# APRS-ESP32_SA8x8_Rev_B.net
KiCad netlist of a schematic drawn in EAGLE
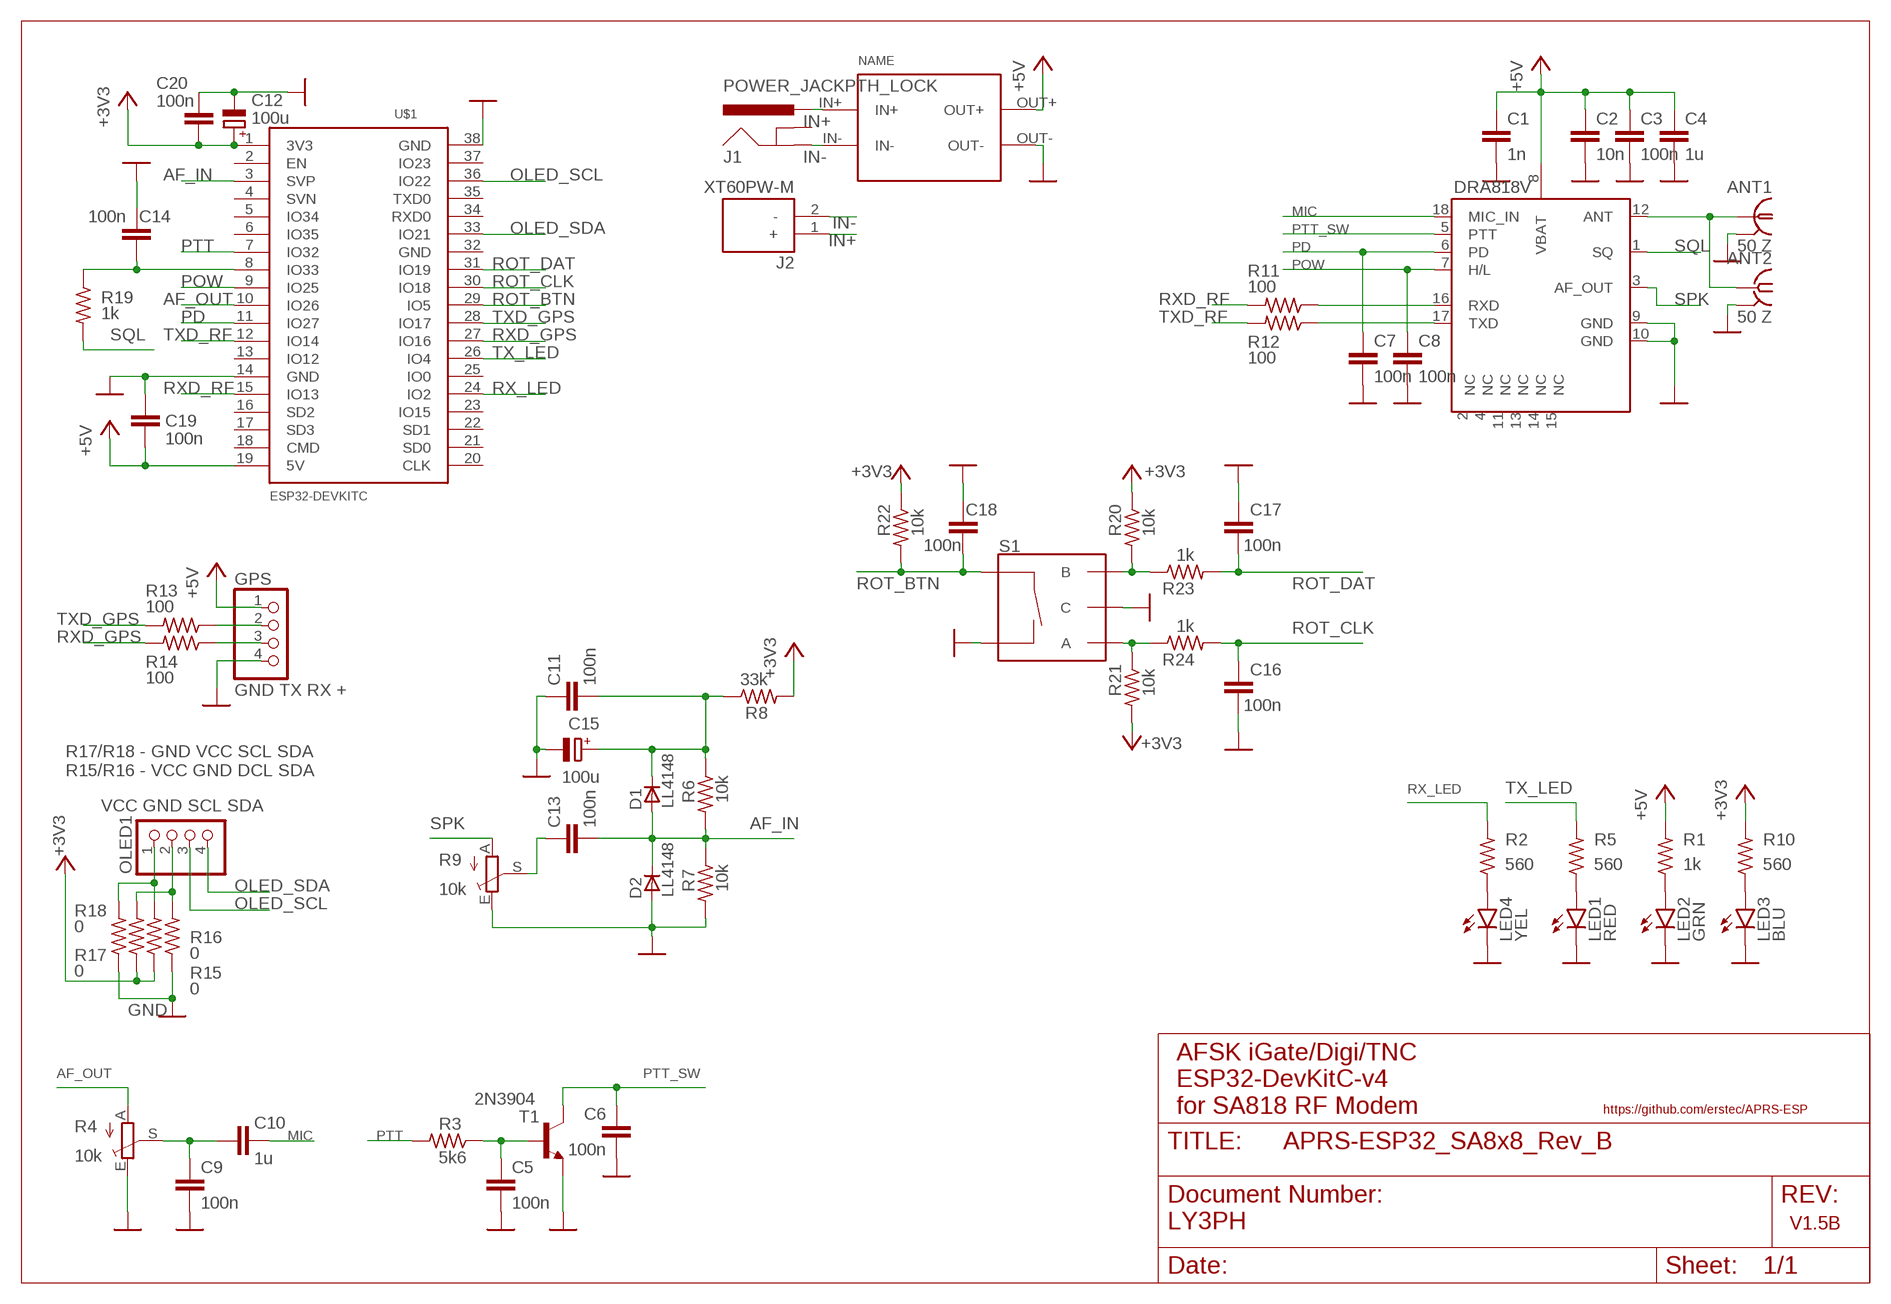
[diagram p0: schematic, sheet 1]

(export (version "E")
  (design (tool "Eeschema 10.0.6"))
  (components
    (comp (ref "ANT1")
      (value "50 Z")
      (footprint "eagle-import:LTI-SASF54GT")
      (libsource (lib "eagle-import") (part "LTI-SASF54GT"))
    )
    (comp (ref "ANT2")
      (value "50 Z")
      (footprint "eagle-import:J502-ND-142-0701-801_806")
      (fields (field (name "MF") "JOHNSON COMPONENTS") (field (name "MPN") "142-0701-801"))
      (libsource (lib "eagle-import") (part "SMA-142-0701-801/806"))
    )
    (comp (ref "C1")
      (value "1n")
      (footprint "eagle-import:C0805")
      (libsource (lib "eagle-import") (part "C-EUC0805"))
    )
    (comp (ref "C2")
      (value "10n")
      (footprint "eagle-import:C0805")
      (libsource (lib "eagle-import") (part "C-EUC0805"))
    )
    (comp (ref "C3")
      (value "100n")
      (footprint "eagle-import:C0805")
      (libsource (lib "eagle-import") (part "C-EUC0805"))
    )
    (comp (ref "C4")
      (value "1u")
      (footprint "eagle-import:C0805")
      (libsource (lib "eagle-import") (part "C-EUC0805"))
    )
    (comp (ref "C5")
      (value "100n")
      (footprint "eagle-import:C0805")
      (libsource (lib "eagle-import") (part "C-EUC0805"))
    )
    (comp (ref "C6")
      (value "100n")
      (footprint "eagle-import:C0805")
      (libsource (lib "eagle-import") (part "C-EUC0805"))
    )
    (comp (ref "C7")
      (value "100n")
      (footprint "eagle-import:C0805")
      (libsource (lib "eagle-import") (part "C-EUC0805"))
    )
    (comp (ref "C8")
      (value "100n")
      (footprint "eagle-import:C0805")
      (libsource (lib "eagle-import") (part "C-EUC0805"))
    )
    (comp (ref "C9")
      (value "100n")
      (footprint "eagle-import:C0805")
      (libsource (lib "eagle-import") (part "C-EUC0805"))
    )
    (comp (ref "C10")
      (value "1u")
      (footprint "eagle-import:C0805")
      (libsource (lib "eagle-import") (part "C-EUC0805"))
    )
    (comp (ref "C11")
      (value "100n")
      (footprint "eagle-import:C0805")
      (libsource (lib "eagle-import") (part "C-EUC0805"))
    )
    (comp (ref "C12")
      (value "100u")
      (footprint "eagle-import:SMC_D")
      (libsource (lib "eagle-import") (part "CPOL-EUSMCD"))
    )
    (comp (ref "C13")
      (value "100n")
      (footprint "eagle-import:C0805")
      (libsource (lib "eagle-import") (part "C-EUC0805"))
    )
    (comp (ref "C14")
      (value "100n")
      (footprint "eagle-import:C0805")
      (libsource (lib "eagle-import") (part "C-EUC0805"))
    )
    (comp (ref "C15")
      (value "100u")
      (footprint "eagle-import:SMC_D")
      (libsource (lib "eagle-import") (part "CPOL-EUSMCD"))
    )
    (comp (ref "C16")
      (value "100n")
      (footprint "eagle-import:C0805")
      (libsource (lib "eagle-import") (part "C-EUC0805"))
    )
    (comp (ref "C17")
      (value "100n")
      (footprint "eagle-import:C0805")
      (libsource (lib "eagle-import") (part "C-EUC0805"))
    )
    (comp (ref "C18")
      (value "100n")
      (footprint "eagle-import:C0805")
      (libsource (lib "eagle-import") (part "C-EUC0805"))
    )
    (comp (ref "C19")
      (value "100n")
      (footprint "eagle-import:C0805")
      (libsource (lib "eagle-import") (part "C-EUC0805"))
    )
    (comp (ref "C20")
      (value "100n")
      (footprint "eagle-import:C0805")
      (libsource (lib "eagle-import") (part "C-EUC0805"))
    )
    (comp (ref "D1")
      (value "LL4148")
      (footprint "eagle-import:SOD80_DO213AA_MINIMELF")
      (libsource (lib "eagle-import") (part "LL4148"))
    )
    (comp (ref "D2")
      (value "LL4148")
      (footprint "eagle-import:SOD80_DO213AA_MINIMELF")
      (libsource (lib "eagle-import") (part "LL4148"))
    )
    (comp (ref "DRA818V")
      (value "DRA818A")
      (footprint "eagle-import:DRA818A")
      (libsource (lib "eagle-import") (part "DRA818A"))
    )
    (comp (ref "GPS")
      (value "GND TX RX +")
      (footprint "eagle-import:1X04")
      (libsource (lib "eagle-import") (part "PINHD-1X4"))
    )
    (comp (ref "J1")
      (value "POWER_JACKPTH_LOCK")
      (footprint "eagle-import:POWER_JACK_PTH_LOCK")
      (libsource (lib "eagle-import") (part "POWER_JACKPTH_LOCK"))
    )
    (comp (ref "J2")
      (value "XT60PW-M")
      (footprint "eagle-import:AMASS_XT60PW-M")
      (fields (field (name "MF") "AMASS"))
      (libsource (lib "eagle-import") (part "XT60PW-M"))
    )
    (comp (ref "LED1")
      (value "RED")
      (footprint "eagle-import:CHIP-LED0805")
      (libsource (lib "eagle-import") (part "LEDCHIP-LED0805"))
    )
    (comp (ref "LED2")
      (value "GRN")
      (footprint "eagle-import:CHIP-LED0805")
      (libsource (lib "eagle-import") (part "LEDCHIP-LED0805"))
    )
    (comp (ref "LED3")
      (value "BLU")
      (footprint "eagle-import:CHIP-LED0805")
      (libsource (lib "eagle-import") (part "LEDCHIP-LED0805"))
    )
    (comp (ref "LED4")
      (value "YEL")
      (footprint "eagle-import:CHIP-LED0805")
      (libsource (lib "eagle-import") (part "LEDCHIP-LED0805"))
    )
    (comp (ref "OLED1")
      (value "VCC GND SCL SDA")
      (footprint "eagle-import:1X04")
      (libsource (lib "eagle-import") (part "PINHD-1X4"))
    )
    (comp (ref "R1")
      (value "1k")
      (footprint "eagle-import:R0805")
      (libsource (lib "eagle-import") (part "R-US_R0805"))
    )
    (comp (ref "R2")
      (value "560")
      (footprint "eagle-import:R0805")
      (libsource (lib "eagle-import") (part "R-US_R0805"))
    )
    (comp (ref "R3")
      (value "5k6")
      (footprint "eagle-import:R0805")
      (libsource (lib "eagle-import") (part "R-US_R0805"))
    )
    (comp (ref "R4")
      (value "10k")
      (footprint "eagle-import:CA6H")
      (libsource (lib "eagle-import") (part "TRIM_EU-CA6H"))
    )
    (comp (ref "R5")
      (value "560")
      (footprint "eagle-import:R0805")
      (libsource (lib "eagle-import") (part "R-US_R0805"))
    )
    (comp (ref "R6")
      (value "10k")
      (footprint "eagle-import:R0805")
      (libsource (lib "eagle-import") (part "R-US_R0805"))
    )
    (comp (ref "R7")
      (value "10k")
      (footprint "eagle-import:R0805")
      (libsource (lib "eagle-import") (part "R-US_R0805"))
    )
    (comp (ref "R8")
      (value "33k")
      (footprint "eagle-import:R0805")
      (libsource (lib "eagle-import") (part "R-US_R0805"))
    )
    (comp (ref "R9")
      (value "10k")
      (footprint "eagle-import:CA6H")
      (libsource (lib "eagle-import") (part "TRIM_EU-CA6H"))
    )
    (comp (ref "R10")
      (value "560")
      (footprint "eagle-import:R0805")
      (libsource (lib "eagle-import") (part "R-US_R0805"))
    )
    (comp (ref "R11")
      (value "100")
      (footprint "eagle-import:R0805")
      (libsource (lib "eagle-import") (part "R-US_R0805"))
    )
    (comp (ref "R12")
      (value "100")
      (footprint "eagle-import:R0805")
      (libsource (lib "eagle-import") (part "R-US_R0805"))
    )
    (comp (ref "R13")
      (value "100")
      (footprint "eagle-import:R0805")
      (libsource (lib "eagle-import") (part "R-US_R0805"))
    )
    (comp (ref "R14")
      (value "100")
      (footprint "eagle-import:R0805")
      (libsource (lib "eagle-import") (part "R-US_R0805"))
    )
    (comp (ref "R15")
      (value "0")
      (footprint "eagle-import:R0805")
      (libsource (lib "eagle-import") (part "R-US_R0805"))
    )
    (comp (ref "R16")
      (value "0")
      (footprint "eagle-import:R0805")
      (libsource (lib "eagle-import") (part "R-US_R0805"))
    )
    (comp (ref "R17")
      (value "0")
      (footprint "eagle-import:R0805")
      (libsource (lib "eagle-import") (part "R-US_R0805"))
    )
    (comp (ref "R18")
      (value "0")
      (footprint "eagle-import:R0805")
      (libsource (lib "eagle-import") (part "R-US_R0805"))
    )
    (comp (ref "R19")
      (value "1k")
      (footprint "eagle-import:R0805")
      (libsource (lib "eagle-import") (part "R-US_R0805"))
    )
    (comp (ref "R20")
      (value "10k")
      (footprint "eagle-import:R0805")
      (libsource (lib "eagle-import") (part "R-US_R0805"))
    )
    (comp (ref "R21")
      (value "10k")
      (footprint "eagle-import:R0805")
      (libsource (lib "eagle-import") (part "R-US_R0805"))
    )
    (comp (ref "R22")
      (value "10k")
      (footprint "eagle-import:R0805")
      (libsource (lib "eagle-import") (part "R-US_R0805"))
    )
    (comp (ref "R23")
      (value "1k")
      (footprint "eagle-import:R0805")
      (libsource (lib "eagle-import") (part "R-US_R0805"))
    )
    (comp (ref "R24")
      (value "1k")
      (footprint "eagle-import:R0805")
      (libsource (lib "eagle-import") (part "R-US_R0805"))
    )
    (comp (ref "S1")
      (value "ENCODER-SWITCH")
      (footprint "eagle-import:ROTARY_ENC_PLAIN")
      (libsource (lib "eagle-import") (part "ENCODER-SWITCH"))
    )
    (comp (ref "T1")
      (value "2N3904")
      (footprint "eagle-import:SOT23-BEC")
      (libsource (lib "eagle-import") (part "-NPN-SOT23-BECMMBT3904LT1"))
    )
    (comp (ref "U$1")
      (value "ESP32DEVKITC")
      (footprint "eagle-import:ESP32-DEVKITC")
      (libsource (lib "eagle-import") (part "ESP32DEVKITC"))
    )
    (comp (ref "U$2")
      (value "CP8-ADJ")
      (footprint "eagle-import:CP8-ADJ")
      (libsource (lib "eagle-import") (part "CP8-ADJ"))
    )
  )
  (nets
    (net (code "1") (name "+3V3") (class "Default")
      (node (ref "C12") (pin "+") (pinfunction "+_+") (pintype "passive"))
      (node (ref "C20") (pin "2") (pinfunction "2_2") (pintype "passive"))
      (node (ref "R10") (pin "2") (pinfunction "2_2") (pintype "passive"))
      (node (ref "R15") (pin "1") (pinfunction "1_1") (pintype "passive"))
      (node (ref "R17") (pin "1") (pinfunction "1_1") (pintype "passive"))
      (node (ref "R20") (pin "1") (pinfunction "1_1") (pintype "passive"))
      (node (ref "R21") (pin "2") (pinfunction "2_2") (pintype "passive"))
      (node (ref "R22") (pin "1") (pinfunction "1_1") (pintype "passive"))
      (node (ref "R8") (pin "2") (pinfunction "2_2") (pintype "passive"))
      (node (ref "U$1") (pin "1") (pinfunction "3V3_1") (pintype "bidirectional"))
    )
    (net (code "2") (name "+5V") (class "Default")
      (node (ref "C1") (pin "1") (pinfunction "1_1") (pintype "passive"))
      (node (ref "C19") (pin "2") (pinfunction "2_2") (pintype "passive"))
      (node (ref "C2") (pin "1") (pinfunction "1_1") (pintype "passive"))
      (node (ref "C3") (pin "1") (pinfunction "1_1") (pintype "passive"))
      (node (ref "C4") (pin "1") (pinfunction "1_1") (pintype "passive"))
      (node (ref "DRA818V") (pin "8") (pinfunction "VBAT_8") (pintype "bidirectional"))
      (node (ref "GPS") (pin "1") (pinfunction "1_1") (pintype "passive"))
      (node (ref "R1") (pin "2") (pinfunction "2_2") (pintype "passive"))
      (node (ref "U$1") (pin "19") (pinfunction "5V_19") (pintype "bidirectional"))
      (node (ref "U$2") (pin "OUT+") (pinfunction "OUT+_OUT+") (pintype "passive"))
    )
    (net (code "3") (name "/AF_IN") (class "Default")
      (node (ref "C13") (pin "2") (pinfunction "2_2") (pintype "passive"))
      (node (ref "D1") (pin "A") (pinfunction "A_A") (pintype "passive"))
      (node (ref "D2") (pin "C") (pinfunction "C_C") (pintype "passive"))
      (node (ref "R6") (pin "2") (pinfunction "2_2") (pintype "passive"))
      (node (ref "R7") (pin "1") (pinfunction "1_1") (pintype "passive"))
      (node (ref "U$1") (pin "3") (pinfunction "SVP_3") (pintype "bidirectional"))
    )
    (net (code "4") (name "/AF_OUT") (class "Default")
      (node (ref "R4") (pin "A") (pinfunction "A_A") (pintype "passive"))
      (node (ref "U$1") (pin "10") (pinfunction "IO26_10") (pintype "bidirectional"))
    )
    (net (code "5") (name "/IN+") (class "Default")
      (node (ref "J1") (pin "PWR") (pinfunction "PWR_PWR") (pintype "bidirectional"))
      (node (ref "J2") (pin "1") (pinfunction "+_1") (pintype "passive"))
      (node (ref "U$2") (pin "IN+") (pinfunction "IN+_IN+") (pintype "passive"))
    )
    (net (code "6") (name "/IN-") (class "Default")
      (node (ref "J1") (pin "GND") (pinfunction "GND_GND") (pintype "bidirectional"))
      (node (ref "J2") (pin "2") (pinfunction "-_2") (pintype "passive"))
      (node (ref "U$2") (pin "IN-") (pinfunction "IN-_IN-") (pintype "passive"))
    )
    (net (code "7") (name "/MIC") (class "Default")
      (node (ref "C10") (pin "2") (pinfunction "2_2") (pintype "passive"))
      (node (ref "DRA818V") (pin "18") (pinfunction "MIC_IN_18") (pintype "bidirectional"))
    )
    (net (code "8") (name "/OLED_SCL") (class "Default")
      (node (ref "OLED1") (pin "3") (pinfunction "3_3") (pintype "passive"))
      (node (ref "U$1") (pin "36") (pinfunction "IO22_36") (pintype "bidirectional"))
    )
    (net (code "9") (name "/OLED_SDA") (class "Default")
      (node (ref "OLED1") (pin "4") (pinfunction "4_4") (pintype "passive"))
      (node (ref "U$1") (pin "33") (pinfunction "IO21_33") (pintype "bidirectional"))
    )
    (net (code "10") (name "/PD") (class "Default")
      (node (ref "C7") (pin "1") (pinfunction "1_1") (pintype "passive"))
      (node (ref "DRA818V") (pin "6") (pinfunction "PD_6") (pintype "bidirectional"))
      (node (ref "U$1") (pin "11") (pinfunction "IO27_11") (pintype "bidirectional"))
    )
    (net (code "11") (name "/POW") (class "Default")
      (node (ref "C8") (pin "1") (pinfunction "1_1") (pintype "passive"))
      (node (ref "DRA818V") (pin "7") (pinfunction "H/L_7") (pintype "bidirectional"))
      (node (ref "U$1") (pin "9") (pinfunction "IO25_9") (pintype "bidirectional"))
    )
    (net (code "12") (name "/PTT") (class "Default")
      (node (ref "R3") (pin "2") (pinfunction "2_2") (pintype "passive"))
      (node (ref "U$1") (pin "7") (pinfunction "IO32_7") (pintype "bidirectional"))
    )
    (net (code "13") (name "/PTT_SW") (class "Default")
      (node (ref "C6") (pin "1") (pinfunction "1_1") (pintype "passive"))
      (node (ref "DRA818V") (pin "5") (pinfunction "PTT_5") (pintype "bidirectional"))
      (node (ref "T1") (pin "C") (pinfunction "C_C") (pintype "passive"))
    )
    (net (code "14") (name "/ROT_BTN") (class "Default")
      (node (ref "C18") (pin "2") (pinfunction "2_2") (pintype "passive"))
      (node (ref "R22") (pin "2") (pinfunction "2_2") (pintype "passive"))
      (node (ref "S1") (pin "SW+") (pinfunction "SW+_SW+") (pintype "bidirectional"))
      (node (ref "U$1") (pin "29") (pinfunction "IO5_29") (pintype "bidirectional"))
    )
    (net (code "15") (name "/ROT_CLK") (class "Default")
      (node (ref "C16") (pin "1") (pinfunction "1_1") (pintype "passive"))
      (node (ref "R24") (pin "2") (pinfunction "2_2") (pintype "passive"))
      (node (ref "U$1") (pin "30") (pinfunction "IO18_30") (pintype "bidirectional"))
    )
    (net (code "16") (name "/ROT_DAT") (class "Default")
      (node (ref "C17") (pin "2") (pinfunction "2_2") (pintype "passive"))
      (node (ref "R23") (pin "2") (pinfunction "2_2") (pintype "passive"))
      (node (ref "U$1") (pin "31") (pinfunction "IO19_31") (pintype "bidirectional"))
    )
    (net (code "17") (name "/RXD_GPS") (class "Default")
      (node (ref "R14") (pin "2") (pinfunction "2_2") (pintype "passive"))
      (node (ref "U$1") (pin "27") (pinfunction "IO16_27") (pintype "bidirectional"))
    )
    (net (code "18") (name "/RXD_RF") (class "Default")
      (node (ref "R11") (pin "2") (pinfunction "2_2") (pintype "passive"))
      (node (ref "U$1") (pin "15") (pinfunction "IO13_15") (pintype "bidirectional"))
    )
    (net (code "19") (name "/RX_LED") (class "Default")
      (node (ref "R2") (pin "2") (pinfunction "2_2") (pintype "passive"))
      (node (ref "U$1") (pin "24") (pinfunction "IO2_24") (pintype "bidirectional"))
    )
    (net (code "20") (name "/SPK") (class "Default")
      (node (ref "DRA818V") (pin "3") (pinfunction "AF_OUT_3") (pintype "bidirectional"))
      (node (ref "R9") (pin "A") (pinfunction "A_A") (pintype "passive"))
    )
    (net (code "21") (name "/SQL") (class "Default")
      (node (ref "DRA818V") (pin "1") (pinfunction "SQ_1") (pintype "bidirectional"))
      (node (ref "R19") (pin "2") (pinfunction "2_2") (pintype "passive"))
    )
    (net (code "22") (name "/TXD_GPS") (class "Default")
      (node (ref "R13") (pin "2") (pinfunction "2_2") (pintype "passive"))
      (node (ref "U$1") (pin "28") (pinfunction "IO17_28") (pintype "bidirectional"))
    )
    (net (code "23") (name "/TXD_RF") (class "Default")
      (node (ref "R12") (pin "2") (pinfunction "2_2") (pintype "passive"))
      (node (ref "U$1") (pin "12") (pinfunction "IO14_12") (pintype "bidirectional"))
    )
    (net (code "24") (name "/TX_LED") (class "Default")
      (node (ref "R5") (pin "2") (pinfunction "2_2") (pintype "passive"))
      (node (ref "U$1") (pin "26") (pinfunction "IO4_26") (pintype "bidirectional"))
    )
    (net (code "25") (name "GND") (class "Default")
      (node (ref "ANT1") (pin "2") (pinfunction "2_2") (pintype "passive"))
      (node (ref "ANT1") (pin "3") (pinfunction "2_3") (pintype "passive"))
      (node (ref "ANT1") (pin "4") (pinfunction "2_4") (pintype "passive"))
      (node (ref "ANT1") (pin "5") (pinfunction "2_5") (pintype "passive"))
      (node (ref "ANT2") (pin "G@1") (pinfunction "2_G@1") (pintype "passive"))
      (node (ref "ANT2") (pin "G@2") (pinfunction "2_G@2") (pintype "passive"))
      (node (ref "ANT2") (pin "G@3") (pinfunction "2_G@3") (pintype "passive"))
      (node (ref "ANT2") (pin "G@4") (pinfunction "2_G@4") (pintype "passive"))
      (node (ref "C1") (pin "2") (pinfunction "2_2") (pintype "passive"))
      (node (ref "C11") (pin "1") (pinfunction "1_1") (pintype "passive"))
      (node (ref "C12") (pin "-") (pinfunction "-_-") (pintype "passive"))
      (node (ref "C14") (pin "2") (pinfunction "2_2") (pintype "passive"))
      (node (ref "C15") (pin "-") (pinfunction "-_-") (pintype "passive"))
      (node (ref "C16") (pin "2") (pinfunction "2_2") (pintype "passive"))
      (node (ref "C17") (pin "1") (pinfunction "1_1") (pintype "passive"))
      (node (ref "C18") (pin "1") (pinfunction "1_1") (pintype "passive"))
      (node (ref "C19") (pin "1") (pinfunction "1_1") (pintype "passive"))
      (node (ref "C2") (pin "2") (pinfunction "2_2") (pintype "passive"))
      (node (ref "C20") (pin "1") (pinfunction "1_1") (pintype "passive"))
      (node (ref "C3") (pin "2") (pinfunction "2_2") (pintype "passive"))
      (node (ref "C4") (pin "2") (pinfunction "2_2") (pintype "passive"))
      (node (ref "C5") (pin "2") (pinfunction "2_2") (pintype "passive"))
      (node (ref "C6") (pin "2") (pinfunction "2_2") (pintype "passive"))
      (node (ref "C7") (pin "2") (pinfunction "2_2") (pintype "passive"))
      (node (ref "C8") (pin "2") (pinfunction "2_2") (pintype "passive"))
      (node (ref "C9") (pin "2") (pinfunction "2_2") (pintype "passive"))
      (node (ref "D2") (pin "A") (pinfunction "A_A") (pintype "passive"))
      (node (ref "DRA818V") (pin "10") (pinfunction "GND_10") (pintype "bidirectional"))
      (node (ref "DRA818V") (pin "9") (pinfunction "GND_9") (pintype "bidirectional"))
      (node (ref "GPS") (pin "4") (pinfunction "4_4") (pintype "passive"))
      (node (ref "LED1") (pin "C") (pinfunction "C_C") (pintype "passive"))
      (node (ref "LED2") (pin "C") (pinfunction "C_C") (pintype "passive"))
      (node (ref "LED3") (pin "C") (pinfunction "C_C") (pintype "passive"))
      (node (ref "LED4") (pin "C") (pinfunction "C_C") (pintype "passive"))
      (node (ref "R16") (pin "1") (pinfunction "1_1") (pintype "passive"))
      (node (ref "R18") (pin "1") (pinfunction "1_1") (pintype "passive"))
      (node (ref "R4") (pin "E") (pinfunction "E_E") (pintype "passive"))
      (node (ref "R7") (pin "2") (pinfunction "2_2") (pintype "passive"))
      (node (ref "R9") (pin "E") (pinfunction "E_E") (pintype "passive"))
      (node (ref "S1") (pin "C") (pinfunction "C_C") (pintype "bidirectional"))
      (node (ref "S1") (pin "SW-") (pinfunction "SW-_SW-") (pintype "bidirectional"))
      (node (ref "T1") (pin "E") (pinfunction "E_E") (pintype "passive"))
      (node (ref "U$1") (pin "14") (pinfunction "GND_14") (pintype "bidirectional"))
      (node (ref "U$1") (pin "38") (pinfunction "GND_38") (pintype "bidirectional"))
      (node (ref "U$2") (pin "OUT-") (pinfunction "OUT-_OUT-") (pintype "passive"))
    )
    (net (code "26") (name "Net-(C5-Pad1)") (class "Default")
      (node (ref "C5") (pin "1") (pinfunction "1_1") (pintype "passive"))
      (node (ref "R3") (pin "1") (pinfunction "1_1") (pintype "passive"))
      (node (ref "T1") (pin "B") (pinfunction "B_B") (pintype "passive"))
    )
    (net (code "27") (name "Net-(C10-Pad1)") (class "Default")
      (node (ref "C10") (pin "1") (pinfunction "1_1") (pintype "passive"))
      (node (ref "C9") (pin "1") (pinfunction "1_1") (pintype "passive"))
      (node (ref "R4") (pin "S") (pinfunction "S_S") (pintype "passive"))
    )
    (net (code "28") (name "Net-(C11-Pad2)") (class "Default")
      (node (ref "C11") (pin "2") (pinfunction "2_2") (pintype "passive"))
      (node (ref "C15") (pin "+") (pinfunction "+_+") (pintype "passive"))
      (node (ref "D1") (pin "C") (pinfunction "C_C") (pintype "passive"))
      (node (ref "R6") (pin "1") (pinfunction "1_1") (pintype "passive"))
      (node (ref "R8") (pin "1") (pinfunction "1_1") (pintype "passive"))
    )
    (net (code "29") (name "Net-(C13-Pad1)") (class "Default")
      (node (ref "C13") (pin "1") (pinfunction "1_1") (pintype "passive"))
      (node (ref "R9") (pin "S") (pinfunction "S_S") (pintype "passive"))
    )
    (net (code "30") (name "Net-(DRA818V-ANT)") (class "Default")
      (node (ref "ANT1") (pin "1") (pinfunction "1_1") (pintype "passive"))
      (node (ref "ANT2") (pin "1") (pinfunction "1_1") (pintype "passive"))
      (node (ref "DRA818V") (pin "12") (pinfunction "ANT_12") (pintype "bidirectional"))
    )
    (net (code "31") (name "Net-(DRA818V-RXD)") (class "Default")
      (node (ref "DRA818V") (pin "16") (pinfunction "RXD_16") (pintype "bidirectional"))
      (node (ref "R11") (pin "1") (pinfunction "1_1") (pintype "passive"))
    )
    (net (code "32") (name "Net-(DRA818V-TXD)") (class "Default")
      (node (ref "DRA818V") (pin "17") (pinfunction "TXD_17") (pintype "bidirectional"))
      (node (ref "R12") (pin "1") (pinfunction "1_1") (pintype "passive"))
    )
    (net (code "33") (name "Net-(GPS-Pad2)") (class "Default")
      (node (ref "GPS") (pin "2") (pinfunction "2_2") (pintype "passive"))
      (node (ref "R13") (pin "1") (pinfunction "1_1") (pintype "passive"))
    )
    (net (code "34") (name "Net-(GPS-Pad3)") (class "Default")
      (node (ref "GPS") (pin "3") (pinfunction "3_3") (pintype "passive"))
      (node (ref "R14") (pin "1") (pinfunction "1_1") (pintype "passive"))
    )
    (net (code "35") (name "Net-(LED1-PadA)") (class "Default")
      (node (ref "LED1") (pin "A") (pinfunction "A_A") (pintype "passive"))
      (node (ref "R5") (pin "1") (pinfunction "1_1") (pintype "passive"))
    )
    (net (code "36") (name "Net-(LED2-PadA)") (class "Default")
      (node (ref "LED2") (pin "A") (pinfunction "A_A") (pintype "passive"))
      (node (ref "R1") (pin "1") (pinfunction "1_1") (pintype "passive"))
    )
    (net (code "37") (name "Net-(LED3-PadA)") (class "Default")
      (node (ref "LED3") (pin "A") (pinfunction "A_A") (pintype "passive"))
      (node (ref "R10") (pin "1") (pinfunction "1_1") (pintype "passive"))
    )
    (net (code "38") (name "Net-(LED4-PadA)") (class "Default")
      (node (ref "LED4") (pin "A") (pinfunction "A_A") (pintype "passive"))
      (node (ref "R2") (pin "1") (pinfunction "1_1") (pintype "passive"))
    )
    (net (code "39") (name "Net-(OLED1-Pad1)") (class "Default")
      (node (ref "OLED1") (pin "1") (pinfunction "1_1") (pintype "passive"))
      (node (ref "R15") (pin "2") (pinfunction "2_2") (pintype "passive"))
      (node (ref "R18") (pin "2") (pinfunction "2_2") (pintype "passive"))
    )
    (net (code "40") (name "Net-(OLED1-Pad2)") (class "Default")
      (node (ref "OLED1") (pin "2") (pinfunction "2_2") (pintype "passive"))
      (node (ref "R16") (pin "2") (pinfunction "2_2") (pintype "passive"))
      (node (ref "R17") (pin "2") (pinfunction "2_2") (pintype "passive"))
    )
    (net (code "41") (name "Net-(R20-Pad2)") (class "Default")
      (node (ref "R20") (pin "2") (pinfunction "2_2") (pintype "passive"))
      (node (ref "R23") (pin "1") (pinfunction "1_1") (pintype "passive"))
      (node (ref "S1") (pin "B") (pinfunction "B_B") (pintype "bidirectional"))
    )
    (net (code "42") (name "Net-(R21-Pad1)") (class "Default")
      (node (ref "R21") (pin "1") (pinfunction "1_1") (pintype "passive"))
      (node (ref "R24") (pin "1") (pinfunction "1_1") (pintype "passive"))
      (node (ref "S1") (pin "A") (pinfunction "A_A") (pintype "bidirectional"))
    )
    (net (code "43") (name "Net-(U$1-IO33)") (class "Default")
      (node (ref "C14") (pin "1") (pinfunction "1_1") (pintype "passive"))
      (node (ref "R19") (pin "1") (pinfunction "1_1") (pintype "passive"))
      (node (ref "U$1") (pin "8") (pinfunction "IO33_8") (pintype "bidirectional"))
    )
    (net (code "44") (name "unconnected-(DRA818V-NC-Pad2)") (class "Default")
      (node (ref "DRA818V") (pin "2") (pinfunction "NC_2") (pintype "bidirectional"))
    )
    (net (code "45") (name "unconnected-(DRA818V-NC-Pad4)") (class "Default")
      (node (ref "DRA818V") (pin "4") (pinfunction "NC_4") (pintype "bidirectional"))
    )
    (net (code "46") (name "unconnected-(DRA818V-NC-Pad11)") (class "Default")
      (node (ref "DRA818V") (pin "11") (pinfunction "NC_11") (pintype "bidirectional"))
    )
    (net (code "47") (name "unconnected-(DRA818V-NC-Pad13)") (class "Default")
      (node (ref "DRA818V") (pin "13") (pinfunction "NC_13") (pintype "bidirectional"))
    )
    (net (code "48") (name "unconnected-(DRA818V-NC-Pad14)") (class "Default")
      (node (ref "DRA818V") (pin "14") (pinfunction "NC_14") (pintype "bidirectional"))
    )
    (net (code "49") (name "unconnected-(DRA818V-NC-Pad15)") (class "Default")
      (node (ref "DRA818V") (pin "15") (pinfunction "NC_15") (pintype "bidirectional"))
    )
    (net (code "50") (name "unconnected-(J1-PadGNDBREAK)") (class "Default")
      (node (ref "J1") (pin "GNDBREAK") (pinfunction "GNDBREAK_GNDBREAK") (pintype "bidirectional"))
    )
    (net (code "51") (name "unconnected-(U$1-CLK-Pad20)") (class "Default")
      (node (ref "U$1") (pin "20") (pinfunction "CLK_20") (pintype "bidirectional"))
    )
    (net (code "52") (name "unconnected-(U$1-CMD-Pad18)") (class "Default")
      (node (ref "U$1") (pin "18") (pinfunction "CMD_18") (pintype "bidirectional"))
    )
    (net (code "53") (name "unconnected-(U$1-EN-Pad2)") (class "Default")
      (node (ref "U$1") (pin "2") (pinfunction "EN_2") (pintype "bidirectional"))
    )
    (net (code "54") (name "unconnected-(U$1-GND-Pad32)") (class "Default")
      (node (ref "U$1") (pin "32") (pinfunction "GND_32") (pintype "bidirectional"))
    )
    (net (code "55") (name "unconnected-(U$1-IO0-Pad25)") (class "Default")
      (node (ref "U$1") (pin "25") (pinfunction "IO0_25") (pintype "bidirectional"))
    )
    (net (code "56") (name "unconnected-(U$1-IO12-Pad13)") (class "Default")
      (node (ref "U$1") (pin "13") (pinfunction "IO12_13") (pintype "bidirectional"))
    )
    (net (code "57") (name "unconnected-(U$1-IO15-Pad23)") (class "Default")
      (node (ref "U$1") (pin "23") (pinfunction "IO15_23") (pintype "bidirectional"))
    )
    (net (code "58") (name "unconnected-(U$1-IO23-Pad37)") (class "Default")
      (node (ref "U$1") (pin "37") (pinfunction "IO23_37") (pintype "bidirectional"))
    )
    (net (code "59") (name "unconnected-(U$1-IO34-Pad5)") (class "Default")
      (node (ref "U$1") (pin "5") (pinfunction "IO34_5") (pintype "bidirectional"))
    )
    (net (code "60") (name "unconnected-(U$1-IO35-Pad6)") (class "Default")
      (node (ref "U$1") (pin "6") (pinfunction "IO35_6") (pintype "bidirectional"))
    )
    (net (code "61") (name "unconnected-(U$1-RXD0-Pad34)") (class "Default")
      (node (ref "U$1") (pin "34") (pinfunction "RXD0_34") (pintype "bidirectional"))
    )
    (net (code "62") (name "unconnected-(U$1-SD0-Pad21)") (class "Default")
      (node (ref "U$1") (pin "21") (pinfunction "SD0_21") (pintype "bidirectional"))
    )
    (net (code "63") (name "unconnected-(U$1-SD1-Pad22)") (class "Default")
      (node (ref "U$1") (pin "22") (pinfunction "SD1_22") (pintype "bidirectional"))
    )
    (net (code "64") (name "unconnected-(U$1-SD2-Pad16)") (class "Default")
      (node (ref "U$1") (pin "16") (pinfunction "SD2_16") (pintype "bidirectional"))
    )
    (net (code "65") (name "unconnected-(U$1-SD3-Pad17)") (class "Default")
      (node (ref "U$1") (pin "17") (pinfunction "SD3_17") (pintype "bidirectional"))
    )
    (net (code "66") (name "unconnected-(U$1-SVN-Pad4)") (class "Default")
      (node (ref "U$1") (pin "4") (pinfunction "SVN_4") (pintype "bidirectional"))
    )
    (net (code "67") (name "unconnected-(U$1-TXD0-Pad35)") (class "Default")
      (node (ref "U$1") (pin "35") (pinfunction "TXD0_35") (pintype "bidirectional"))
    )
  )
)
